# fablab_example_board.net
KiCad netlist of a schematic drawn in EAGLE
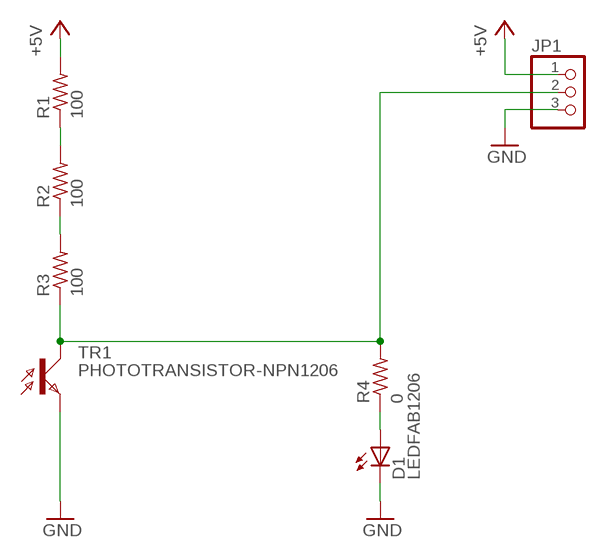
[diagram p0: schematic, sheet 1]

(export (version "E")
  (design (tool "Eeschema 10.0.6"))
  (components
    (comp (ref "D1")
      (value "LEDFAB1206")
      (footprint "eagle-import:LED1206FAB")
      (libsource (lib "eagle-import") (part "LEDFAB1206"))
    )
    (comp (ref "JP1")
      (value "PINHD-1X3")
      (footprint "eagle-import:1X03")
      (libsource (lib "eagle-import") (part "PINHD-1X3"))
    )
    (comp (ref "R1")
      (value "100")
      (footprint "eagle-import:R1206FAB")
      (libsource (lib "eagle-import") (part "RES-US1206FAB"))
    )
    (comp (ref "R2")
      (value "100")
      (footprint "eagle-import:R1206FAB")
      (libsource (lib "eagle-import") (part "RES-US1206FAB"))
    )
    (comp (ref "R3")
      (value "100")
      (footprint "eagle-import:R1206FAB")
      (libsource (lib "eagle-import") (part "RES-US1206FAB"))
    )
    (comp (ref "R4")
      (value "0")
      (footprint "eagle-import:R1206FAB")
      (libsource (lib "eagle-import") (part "RES-US1206FAB"))
    )
    (comp (ref "TR1")
      (value "PHOTOTRANSISTOR-NPN1206")
      (footprint "eagle-import:OP1206")
      (libsource (lib "eagle-import") (part "PHOTOTRANSISTOR-NPN1206"))
    )
  )
  (nets
    (net (code "1") (name "+5V") (class "Default")
      (node (ref "JP1") (pin "1") (pinfunction "1_1") (pintype "passive"))
      (node (ref "R1") (pin "2") (pinfunction "2_2") (pintype "passive"))
    )
    (net (code "2") (name "GND") (class "Default")
      (node (ref "D1") (pin "2") (pinfunction "C_2") (pintype "passive"))
      (node (ref "JP1") (pin "3") (pinfunction "3_3") (pintype "passive"))
      (node (ref "TR1") (pin "E") (pinfunction "E_E") (pintype "passive"))
    )
    (net (code "3") (name "Net-(D1-A)") (class "Default")
      (node (ref "D1") (pin "1") (pinfunction "A_1") (pintype "passive"))
      (node (ref "R4") (pin "1") (pinfunction "1_1") (pintype "passive"))
    )
    (net (code "4") (name "Net-(JP1-Pad2)") (class "Default")
      (node (ref "JP1") (pin "2") (pinfunction "2_2") (pintype "passive"))
      (node (ref "R3") (pin "1") (pinfunction "1_1") (pintype "passive"))
      (node (ref "R4") (pin "2") (pinfunction "2_2") (pintype "passive"))
      (node (ref "TR1") (pin "C") (pinfunction "C_C") (pintype "passive"))
    )
    (net (code "5") (name "Net-(R1-Pad1)") (class "Default")
      (node (ref "R1") (pin "1") (pinfunction "1_1") (pintype "passive"))
      (node (ref "R2") (pin "2") (pinfunction "2_2") (pintype "passive"))
    )
    (net (code "6") (name "Net-(R2-Pad1)") (class "Default")
      (node (ref "R2") (pin "1") (pinfunction "1_1") (pintype "passive"))
      (node (ref "R3") (pin "2") (pinfunction "2_2") (pintype "passive"))
    )
  )
)
